# Girraffe_V3_6.net
KiCad netlist of a schematic drawn in EAGLE
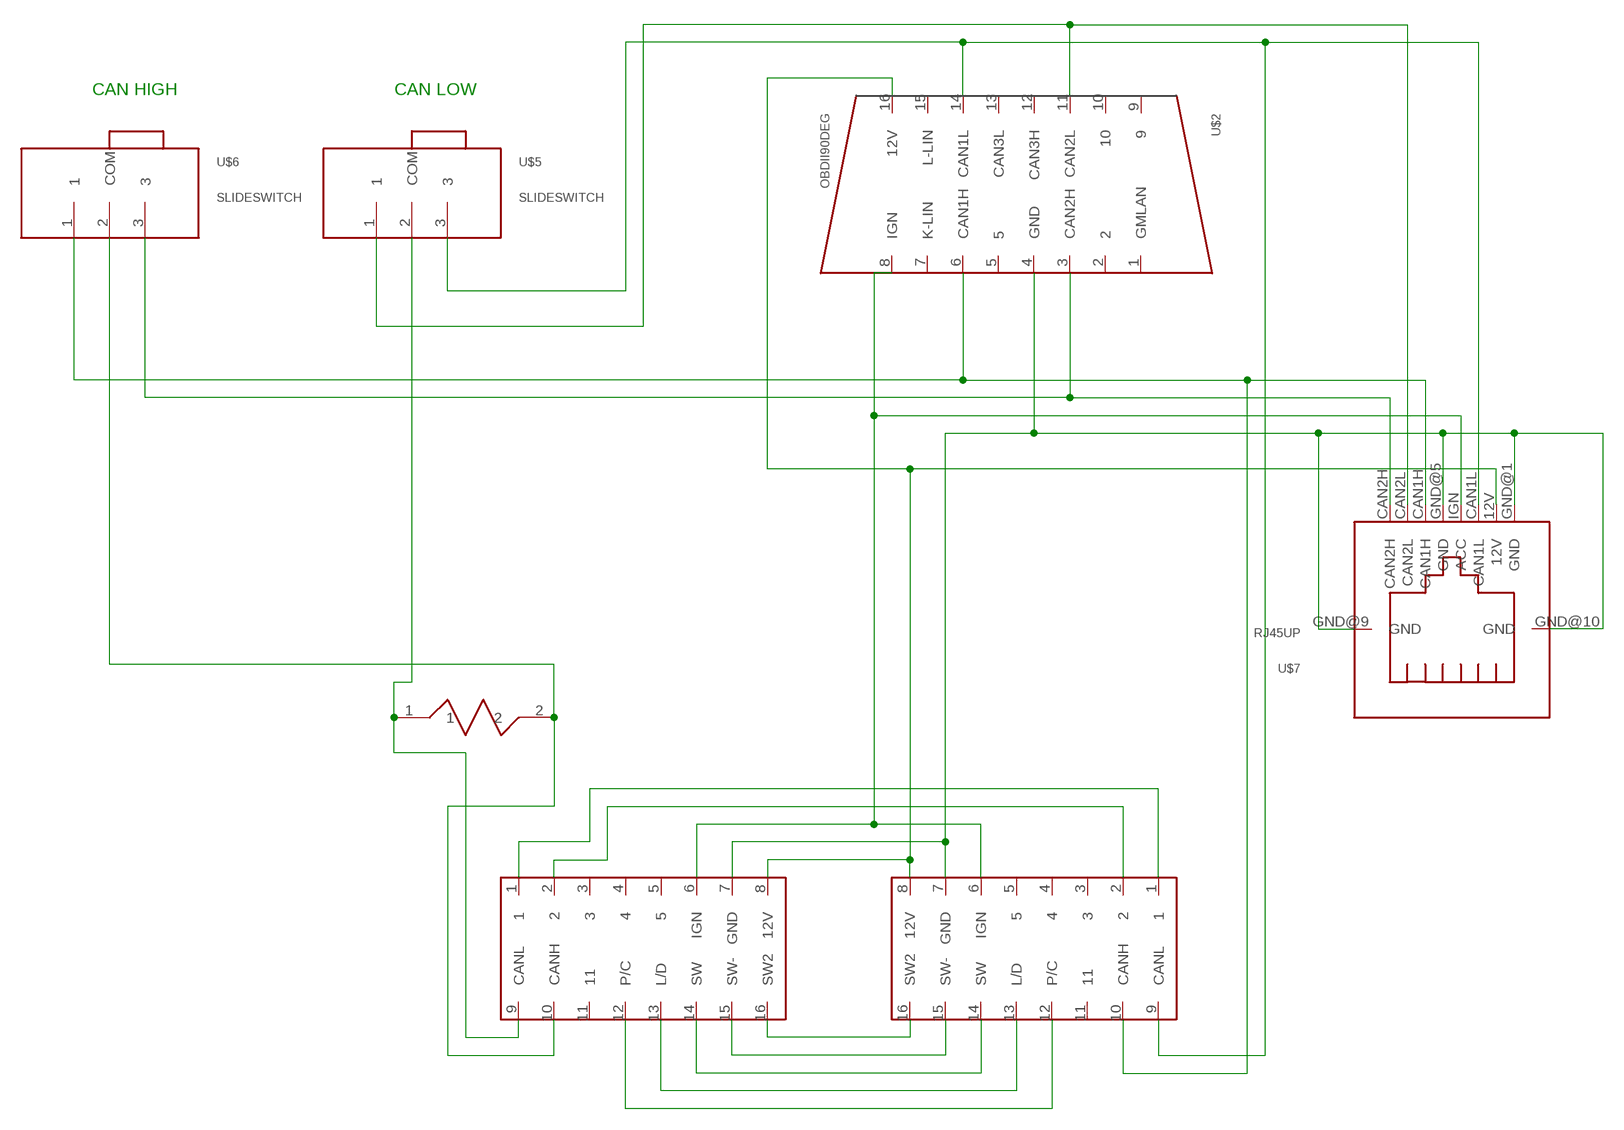
[diagram p0: schematic, sheet 1]

(export (version "E")
  (design (tool "Eeschema 10.0.6"))
  (components
    (comp (ref "U$1")
      (value "120OHM")
      (footprint "eagle-import:120OHM")
      (libsource (lib "eagle-import") (part "120OHM"))
    )
    (comp (ref "U$2")
      (value "OBDII90DEG")
      (footprint "eagle-import:OBDII")
      (libsource (lib "eagle-import") (part "OBDII90DEG"))
    )
    (comp (ref "U$3")
      (value "R137IN")
      (footprint "eagle-import:R137")
      (libsource (lib "eagle-import") (part "R137IN"))
    )
    (comp (ref "U$4")
      (value "R137OUT")
      (footprint "eagle-import:R137OUT")
      (libsource (lib "eagle-import") (part "R137OUT"))
    )
    (comp (ref "U$5")
      (value "SLIDESWITCH")
      (footprint "eagle-import:SLIDESWITCH")
      (libsource (lib "eagle-import") (part "SLIDESWITCH"))
    )
    (comp (ref "U$6")
      (value "SLIDESWITCH")
      (footprint "eagle-import:SLIDESWITCH")
      (libsource (lib "eagle-import") (part "SLIDESWITCH"))
    )
    (comp (ref "U$7")
      (value "RJ45UP")
      (footprint "eagle-import:VERRJ45")
      (libsource (lib "eagle-import") (part "RJ45UP"))
    )
  )
  (nets
    (net (code "1") (name "Net-(U$2-12V)") (class "Default")
      (node (ref "U$2") (pin "16") (pinfunction "12V_16") (pintype "bidirectional"))
      (node (ref "U$3") (pin "8") (pinfunction "12V_8") (pintype "bidirectional"))
      (node (ref "U$4") (pin "8") (pinfunction "12V_8") (pintype "bidirectional"))
      (node (ref "U$7") (pin "12V") (pinfunction "12V_12V") (pintype "bidirectional"))
    )
    (net (code "2") (name "Net-(U$2-CAN1H)") (class "Default")
      (node (ref "U$2") (pin "6") (pinfunction "CAN1H_6") (pintype "bidirectional"))
      (node (ref "U$3") (pin "10") (pinfunction "CANH_10") (pintype "bidirectional"))
      (node (ref "U$6") (pin "1") (pinfunction "1_1") (pintype "input"))
      (node (ref "U$7") (pin "CAN1H") (pinfunction "CAN1H_CAN1H") (pintype "bidirectional"))
    )
    (net (code "3") (name "Net-(U$2-CAN1L)") (class "Default")
      (node (ref "U$2") (pin "14") (pinfunction "CAN1L_14") (pintype "bidirectional"))
      (node (ref "U$3") (pin "9") (pinfunction "CANL_9") (pintype "bidirectional"))
      (node (ref "U$5") (pin "3") (pinfunction "3_3") (pintype "input"))
      (node (ref "U$7") (pin "CAN1L") (pinfunction "CAN1L_CAN1L") (pintype "bidirectional"))
    )
    (net (code "4") (name "Net-(U$2-CAN2H)") (class "Default")
      (node (ref "U$2") (pin "3") (pinfunction "CAN2H_3") (pintype "bidirectional"))
      (node (ref "U$6") (pin "3") (pinfunction "3_3") (pintype "input"))
      (node (ref "U$7") (pin "CAN2H") (pinfunction "CAN2H_CAN2H") (pintype "bidirectional"))
    )
    (net (code "5") (name "Net-(U$2-CAN2L)") (class "Default")
      (node (ref "U$2") (pin "11") (pinfunction "CAN2L_11") (pintype "bidirectional"))
      (node (ref "U$5") (pin "1") (pinfunction "1_1") (pintype "input"))
      (node (ref "U$7") (pin "CAN2L") (pinfunction "CAN2L_CAN2L") (pintype "bidirectional"))
    )
    (net (code "6") (name "Net-(U$2-GND)") (class "Default")
      (node (ref "U$2") (pin "4") (pinfunction "GND_4") (pintype "bidirectional"))
      (node (ref "U$3") (pin "7") (pinfunction "GND_7") (pintype "bidirectional"))
      (node (ref "U$4") (pin "7") (pinfunction "GND_7") (pintype "bidirectional"))
      (node (ref "U$7") (pin "GND@1") (pinfunction "GND_GND@1") (pintype "bidirectional"))
      (node (ref "U$7") (pin "GND@10") (pinfunction "GND_GND@10") (pintype "bidirectional"))
      (node (ref "U$7") (pin "GND@5") (pinfunction "GND_GND@5") (pintype "bidirectional"))
      (node (ref "U$7") (pin "GND@9") (pinfunction "GND_GND@9") (pintype "bidirectional"))
    )
    (net (code "7") (name "Net-(U$2-IGN)") (class "Default")
      (node (ref "U$2") (pin "8") (pinfunction "IGN_8") (pintype "bidirectional"))
      (node (ref "U$3") (pin "6") (pinfunction "IGN_6") (pintype "bidirectional"))
      (node (ref "U$4") (pin "6") (pinfunction "IGN_6") (pintype "bidirectional"))
      (node (ref "U$7") (pin "IGN") (pinfunction "ACC_IGN") (pintype "bidirectional"))
    )
    (net (code "8") (name "Net-(U$3-L{slash}D)") (class "Default")
      (node (ref "U$3") (pin "13") (pinfunction "L/D_13") (pintype "bidirectional"))
      (node (ref "U$4") (pin "13") (pinfunction "L/D_13") (pintype "bidirectional"))
    )
    (net (code "9") (name "Net-(U$3-Pad1)") (class "Default")
      (node (ref "U$3") (pin "1") (pinfunction "1_1") (pintype "bidirectional"))
      (node (ref "U$4") (pin "1") (pinfunction "1_1") (pintype "bidirectional"))
    )
    (net (code "10") (name "Net-(U$3-Pad2)") (class "Default")
      (node (ref "U$3") (pin "2") (pinfunction "2_2") (pintype "bidirectional"))
      (node (ref "U$4") (pin "2") (pinfunction "2_2") (pintype "bidirectional"))
    )
    (net (code "11") (name "Net-(U$3-P{slash}C)") (class "Default")
      (node (ref "U$3") (pin "12") (pinfunction "P/C_12") (pintype "bidirectional"))
      (node (ref "U$4") (pin "12") (pinfunction "P/C_12") (pintype "bidirectional"))
    )
    (net (code "12") (name "Net-(U$3-SW)") (class "Default")
      (node (ref "U$3") (pin "14") (pinfunction "SW_14") (pintype "bidirectional"))
      (node (ref "U$4") (pin "14") (pinfunction "SW_14") (pintype "bidirectional"))
    )
    (net (code "13") (name "Net-(U$3-SW-)") (class "Default")
      (node (ref "U$3") (pin "15") (pinfunction "SW-_15") (pintype "bidirectional"))
      (node (ref "U$4") (pin "15") (pinfunction "SW-_15") (pintype "bidirectional"))
    )
    (net (code "14") (name "Net-(U$3-SW2)") (class "Default")
      (node (ref "U$3") (pin "16") (pinfunction "SW2_16") (pintype "bidirectional"))
      (node (ref "U$4") (pin "16") (pinfunction "SW2_16") (pintype "bidirectional"))
    )
    (net (code "15") (name "Net-(U$4-CANH)") (class "Default")
      (node (ref "U$1") (pin "2") (pinfunction "2_2") (pintype "bidirectional"))
      (node (ref "U$4") (pin "10") (pinfunction "CANH_10") (pintype "bidirectional"))
      (node (ref "U$6") (pin "2") (pinfunction "COM_2") (pintype "output"))
    )
    (net (code "16") (name "Net-(U$4-CANL)") (class "Default")
      (node (ref "U$1") (pin "1") (pinfunction "1_1") (pintype "bidirectional"))
      (node (ref "U$4") (pin "9") (pinfunction "CANL_9") (pintype "bidirectional"))
      (node (ref "U$5") (pin "2") (pinfunction "COM_2") (pintype "output"))
    )
    (net (code "17") (name "unconnected-(U$2-CAN3H-Pad12)") (class "Default")
      (node (ref "U$2") (pin "12") (pinfunction "CAN3H_12") (pintype "bidirectional"))
    )
    (net (code "18") (name "unconnected-(U$2-CAN3L-Pad13)") (class "Default")
      (node (ref "U$2") (pin "13") (pinfunction "CAN3L_13") (pintype "bidirectional"))
    )
    (net (code "19") (name "unconnected-(U$2-GMLAN-Pad1)") (class "Default")
      (node (ref "U$2") (pin "1") (pinfunction "GMLAN_1") (pintype "bidirectional"))
    )
    (net (code "20") (name "unconnected-(U$2-K-LIN-Pad7)") (class "Default")
      (node (ref "U$2") (pin "7") (pinfunction "K-LIN_7") (pintype "bidirectional"))
    )
    (net (code "21") (name "unconnected-(U$2-L-LIN-Pad15)") (class "Default")
      (node (ref "U$2") (pin "15") (pinfunction "L-LIN_15") (pintype "bidirectional"))
    )
    (net (code "22") (name "unconnected-(U$2-Pad2)") (class "Default")
      (node (ref "U$2") (pin "2") (pinfunction "2_2") (pintype "bidirectional"))
    )
    (net (code "23") (name "unconnected-(U$2-Pad5)") (class "Default")
      (node (ref "U$2") (pin "5") (pinfunction "5_5") (pintype "bidirectional"))
    )
    (net (code "24") (name "unconnected-(U$2-Pad9)") (class "Default")
      (node (ref "U$2") (pin "9") (pinfunction "9_9") (pintype "bidirectional"))
    )
    (net (code "25") (name "unconnected-(U$2-Pad10)") (class "Default")
      (node (ref "U$2") (pin "10") (pinfunction "10_10") (pintype "bidirectional"))
    )
    (net (code "26") (name "unconnected-(U$3-Pad3)") (class "Default")
      (node (ref "U$3") (pin "3") (pinfunction "3_3") (pintype "bidirectional"))
    )
    (net (code "27") (name "unconnected-(U$3-Pad4)") (class "Default")
      (node (ref "U$3") (pin "4") (pinfunction "4_4") (pintype "bidirectional"))
    )
    (net (code "28") (name "unconnected-(U$3-Pad5)") (class "Default")
      (node (ref "U$3") (pin "5") (pinfunction "5_5") (pintype "bidirectional"))
    )
    (net (code "29") (name "unconnected-(U$3-Pad11)") (class "Default")
      (node (ref "U$3") (pin "11") (pinfunction "11_11") (pintype "bidirectional"))
    )
    (net (code "30") (name "unconnected-(U$4-Pad3)") (class "Default")
      (node (ref "U$4") (pin "3") (pinfunction "3_3") (pintype "bidirectional"))
    )
    (net (code "31") (name "unconnected-(U$4-Pad4)") (class "Default")
      (node (ref "U$4") (pin "4") (pinfunction "4_4") (pintype "bidirectional"))
    )
    (net (code "32") (name "unconnected-(U$4-Pad5)") (class "Default")
      (node (ref "U$4") (pin "5") (pinfunction "5_5") (pintype "bidirectional"))
    )
    (net (code "33") (name "unconnected-(U$4-Pad11)") (class "Default")
      (node (ref "U$4") (pin "11") (pinfunction "11_11") (pintype "bidirectional"))
    )
  )
)
